# start_stop.net
KiCad netlist of a schematic drawn in EAGLE
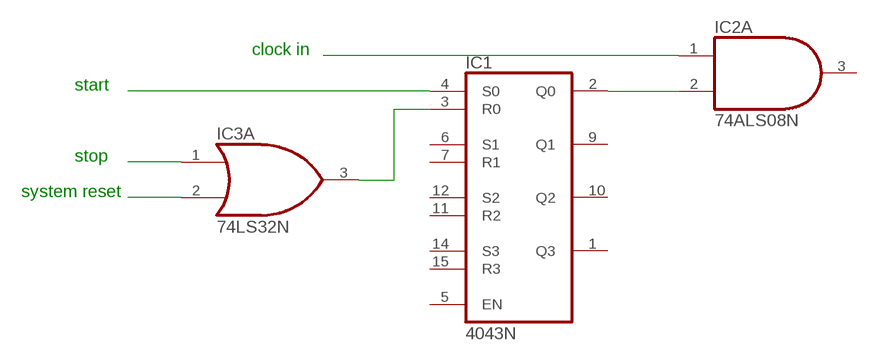
[diagram p0: schematic, sheet 1]

(export (version "E")
  (design (tool "Eeschema 10.0.6"))
  (components
    (comp (ref "IC1")
      (value "4043N")
      (footprint "eagle-import:DIL16")
      (libsource (lib "eagle-import") (part "4043N"))
    )
    (comp (ref "IC2")
      (value "74ALS08N")
      (footprint "eagle-import:DIL14")
      (libsource (lib "eagle-import") (part "7408NALS"))
    )
    (comp (ref "IC3")
      (value "74LS32N")
      (footprint "eagle-import:DIL14")
      (libsource (lib "eagle-import") (part "7432NLS"))
    )
  )
  (nets
    (net (code "1") (name "Net-(IC1A-Q0)") (class "Default")
      (node (ref "IC1") (pin "2") (pinfunction "Q0_2") (pintype "output"))
      (node (ref "IC2") (pin "2") (pinfunction "I1_2") (pintype "input"))
    )
    (net (code "2") (name "Net-(IC1A-R0)") (class "Default")
      (node (ref "IC1") (pin "3") (pinfunction "R0_3") (pintype "input"))
      (node (ref "IC3") (pin "3") (pinfunction "O_3") (pintype "output"))
    )
    (net (code "3") (name "unconnected-(IC1A-EN-Pad5)") (class "Default")
      (node (ref "IC1") (pin "5") (pinfunction "EN_5") (pintype "input"))
    )
    (net (code "4") (name "unconnected-(IC1A-Q1-Pad9)") (class "Default")
      (node (ref "IC1") (pin "9") (pinfunction "Q1_9") (pintype "output"))
    )
    (net (code "5") (name "unconnected-(IC1A-Q2-Pad10)") (class "Default")
      (node (ref "IC1") (pin "10") (pinfunction "Q2_10") (pintype "output"))
    )
    (net (code "6") (name "unconnected-(IC1A-Q3-Pad1)") (class "Default")
      (node (ref "IC1") (pin "1") (pinfunction "Q3_1") (pintype "output"))
    )
    (net (code "7") (name "unconnected-(IC1A-R1-Pad7)") (class "Default")
      (node (ref "IC1") (pin "7") (pinfunction "R1_7") (pintype "input"))
    )
    (net (code "8") (name "unconnected-(IC1A-R2-Pad11)") (class "Default")
      (node (ref "IC1") (pin "11") (pinfunction "R2_11") (pintype "input"))
    )
    (net (code "9") (name "unconnected-(IC1A-R3-Pad15)") (class "Default")
      (node (ref "IC1") (pin "15") (pinfunction "R3_15") (pintype "input"))
    )
    (net (code "10") (name "unconnected-(IC1A-S0-Pad4)") (class "Default")
      (node (ref "IC1") (pin "4") (pinfunction "S0_4") (pintype "input"))
    )
    (net (code "11") (name "unconnected-(IC1A-S1-Pad6)") (class "Default")
      (node (ref "IC1") (pin "6") (pinfunction "S1_6") (pintype "input"))
    )
    (net (code "12") (name "unconnected-(IC1A-S2-Pad12)") (class "Default")
      (node (ref "IC1") (pin "12") (pinfunction "S2_12") (pintype "input"))
    )
    (net (code "13") (name "unconnected-(IC1A-S3-Pad14)") (class "Default")
      (node (ref "IC1") (pin "14") (pinfunction "S3_14") (pintype "input"))
    )
    (net (code "14") (name "unconnected-(IC2A-I0-Pad1)") (class "Default")
      (node (ref "IC2") (pin "1") (pinfunction "I0_1") (pintype "input"))
    )
    (net (code "15") (name "unconnected-(IC2A-O-Pad3)") (class "Default")
      (node (ref "IC2") (pin "3") (pinfunction "O_3") (pintype "output"))
    )
    (net (code "16") (name "unconnected-(IC3A-I0-Pad1)") (class "Default")
      (node (ref "IC3") (pin "1") (pinfunction "I0_1") (pintype "input"))
    )
    (net (code "17") (name "unconnected-(IC3A-I1-Pad2)") (class "Default")
      (node (ref "IC3") (pin "2") (pinfunction "I1_2") (pintype "input"))
    )
  )
)
